# RF_AMP.net
KiCad netlist of a schematic drawn in Altium Designer
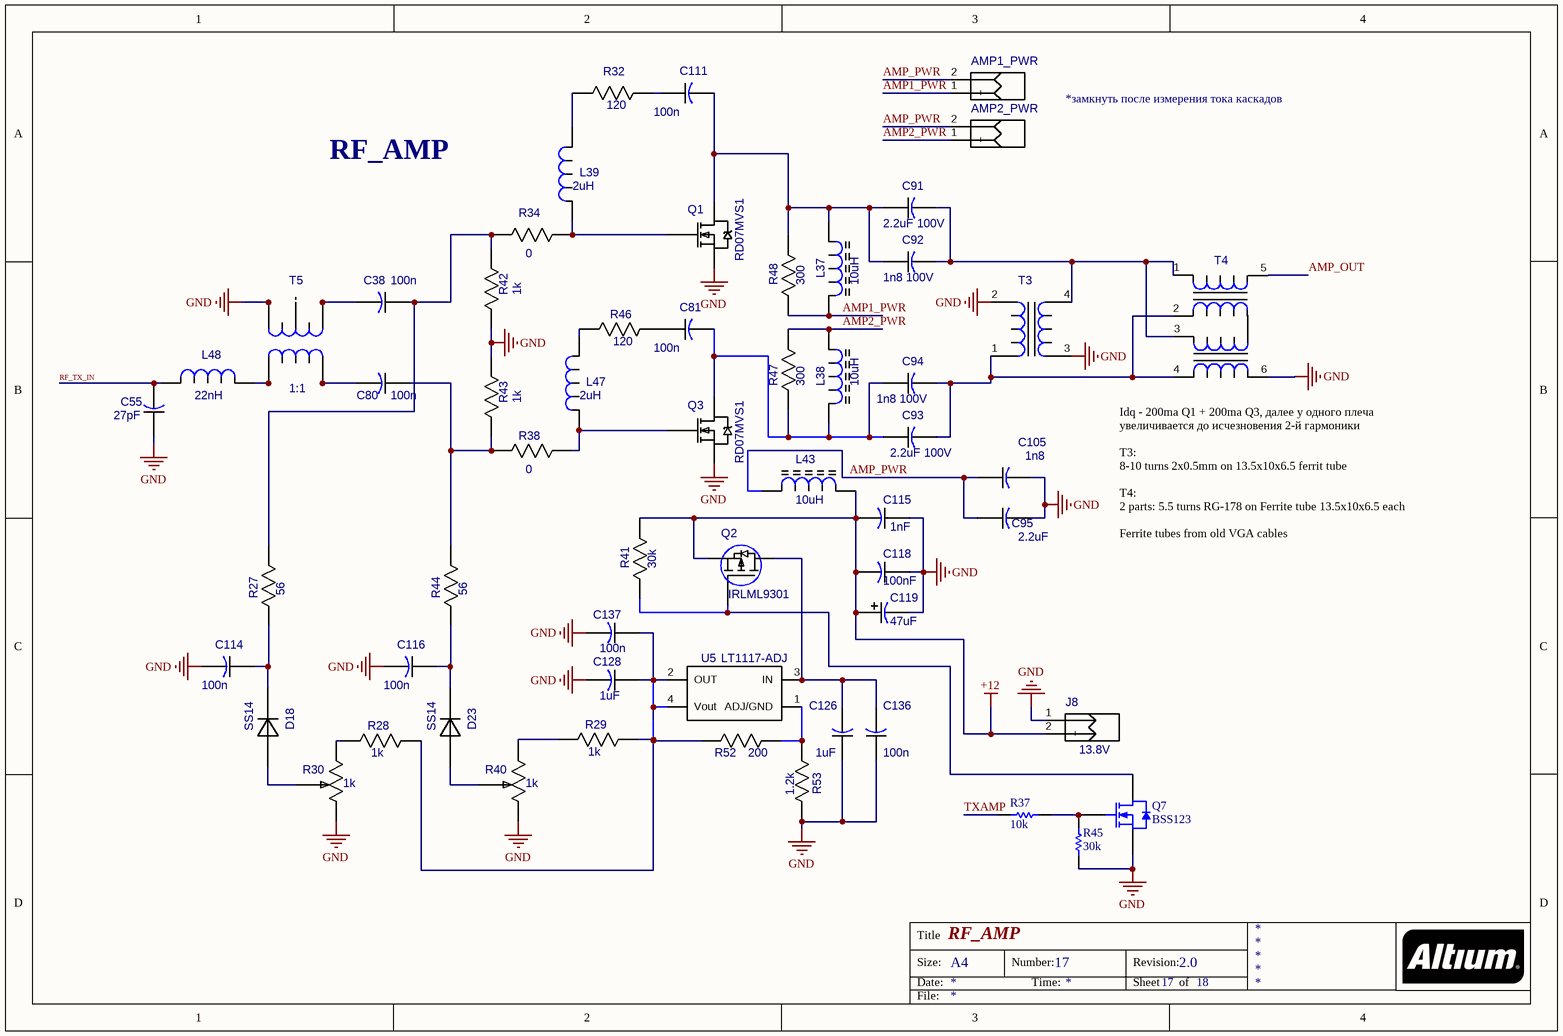
[diagram p0: RF_AMP.SchDoc]

(export (version "E")
  (design (tool "Eeschema 10.0.6"))
  (components
    (comp (ref "AMP1_PWR")
      (value "51022-0200")
      (footprint "51022-0200")
      (libsource (lib "*") (part "51022-0200"))
    )
    (comp (ref "AMP2_PWR")
      (value "51022-0200")
      (footprint "51022-0200")
      (libsource (lib "*") (part "51022-0200"))
    )
    (comp (ref "C38")
      (value "100n")
      (footprint "CAP_0805")
      (description "CAP_0805")
      (libsource (lib "*") (part "CAP_0805"))
    )
    (comp (ref "C55")
      (value "27pF")
      (footprint "CAP_0805")
      (description "CAP_0805")
      (libsource (lib "*") (part "CAP_0805"))
    )
    (comp (ref "C80")
      (value "100n")
      (footprint "CAP_0805")
      (description "CAP_0805")
      (libsource (lib "*") (part "CAP_0805"))
    )
    (comp (ref "C81")
      (value "100n")
      (footprint "CAP_1206")
      (description "CAP_1206")
      (libsource (lib "*") (part "CAP_1206"))
    )
    (comp (ref "C91")
      (value "2.2uF 100V")
      (footprint "CAP_1206")
      (description "CAP_1206")
      (libsource (lib "*") (part "CAP_1206"))
    )
    (comp (ref "C92")
      (value "1n8 100V")
      (footprint "CAP_1206")
      (description "CAP_1206")
      (libsource (lib "*") (part "CAP_1206"))
    )
    (comp (ref "C93")
      (value "2.2uF 100V")
      (footprint "CAP_1206")
      (description "CAP_1206")
      (libsource (lib "*") (part "CAP_1206"))
    )
    (comp (ref "C94")
      (value "1n8 100V")
      (footprint "CAP_1206")
      (description "CAP_1206")
      (libsource (lib "*") (part "CAP_1206"))
    )
    (comp (ref "C95")
      (value "2.2uF")
      (footprint "CAP_1206")
      (description "CAP_1206")
      (libsource (lib "*") (part "CAP_1206"))
    )
    (comp (ref "C105")
      (value "1n8")
      (footprint "CAP_1206")
      (description "CAP_1206")
      (libsource (lib "*") (part "CAP_1206"))
    )
    (comp (ref "C111")
      (value "100n")
      (footprint "CAP_1206")
      (description "CAP_1206")
      (libsource (lib "*") (part "CAP_1206"))
    )
    (comp (ref "C114")
      (value "100n")
      (footprint "CAP_0805")
      (description "CAP_0805")
      (libsource (lib "*") (part "CAP_0805"))
    )
    (comp (ref "C115")
      (value "1nF")
      (footprint "CAP_0805")
      (description "CAP_0805")
      (libsource (lib "*") (part "CAP_0805"))
    )
    (comp (ref "C116")
      (value "100n")
      (footprint "CAP_0805")
      (description "CAP_0805")
      (libsource (lib "*") (part "CAP_0805"))
    )
    (comp (ref "C118")
      (value "100nF")
      (footprint "CAP_0805")
      (description "CAP_0805")
      (libsource (lib "*") (part "CAP_0805"))
    )
    (comp (ref "C119")
      (value "47uF")
      (footprint "CAPAE_6.6x6.6h5.4")
      (description "CAPAE_6.6x6.6h5.4")
      (libsource (lib "*") (part "CAPAE_6.6x6.6h5.4"))
    )
    (comp (ref "C126")
      (value "1uF")
      (footprint "CAP_0805")
      (description "CAP_0805")
      (libsource (lib "*") (part "CAP_0805"))
    )
    (comp (ref "C128")
      (value "1uF")
      (footprint "CAP_0805")
      (description "CAP_0805")
      (libsource (lib "*") (part "CAP_0805"))
    )
    (comp (ref "C136")
      (value "100n")
      (footprint "CAP_0805")
      (description "CAP_0805")
      (libsource (lib "*") (part "CAP_0805"))
    )
    (comp (ref "C137")
      (value "100n")
      (footprint "CAP_0805")
      (description "CAP_0805")
      (libsource (lib "*") (part "CAP_0805"))
    )
    (comp (ref "D18") (value "SS14") (footprint "SS14") (libsource (lib "*") (part "SS14")))
    (comp (ref "D23") (value "SS14") (footprint "SS14") (libsource (lib "*") (part "SS14")))
    (comp (ref "J8")
      (value "13.8V")
      (footprint "1986717-2")
      (description "JX2")
      (libsource (lib "*") (part "1986717-2"))
    )
    (comp (ref "L37")
      (value "10uH")
      (footprint "IND_FERRITE_CORE")
      (description "Inductor")
      (libsource (lib "*") (part "IND_FERRITE_CORE"))
    )
    (comp (ref "L38")
      (value "10uH")
      (footprint "IND_FERRITE_CORE")
      (description "Inductor")
      (libsource (lib "*") (part "IND_FERRITE_CORE"))
    )
    (comp (ref "L39")
      (value "2uH")
      (footprint "IND_0805")
      (description "IND_0805")
      (libsource (lib "*") (part "IND_0805"))
    )
    (comp (ref "L43")
      (value "10uH")
      (footprint "IND_FERRITE_CORE")
      (description "Inductor")
      (libsource (lib "*") (part "IND_FERRITE_CORE"))
    )
    (comp (ref "L47")
      (value "2uH")
      (footprint "IND_0805")
      (description "IND_0805")
      (libsource (lib "*") (part "IND_0805"))
    )
    (comp (ref "L48")
      (value "22nH")
      (footprint "IND_0805")
      (description "IND_0805")
      (libsource (lib "*") (part "IND_0805"))
    )
    (comp (ref "Q1") (value "RD07MVS1") (footprint "RD07MVS1") (libsource (lib "*") (part "RD07MVS1")))
    (comp (ref "Q2")
      (value "IRLML9301")
      (footprint "SOT23")
      (description "MOSFET")
      (libsource (lib "*") (part "MOSFET_ENH_PD"))
    )
    (comp (ref "Q3") (value "RD07MVS1") (footprint "RD07MVS1") (libsource (lib "*") (part "RD07MVS1")))
    (comp (ref "Q7")
      (value "BSS123")
      (footprint "FAIR-SOT23-3_V")
      (fields (field (name "MANUFACTURER") "Fairchild"))
      (libsource (lib "Altium Content Vault") (part "NEMOS-GSD-3"))
    )
    (comp (ref "R27")
      (value "56")
      (footprint "RES_0805")
      (description "RES_0805")
      (libsource (lib "*") (part "RES_0805"))
    )
    (comp (ref "R28")
      (value "1k")
      (footprint "RES_0805")
      (description "RES_0805")
      (libsource (lib "*") (part "RES_0805"))
    )
    (comp (ref "R29")
      (value "1k")
      (footprint "RES_0805")
      (description "RES_0805")
      (libsource (lib "*") (part "RES_0805"))
    )
    (comp (ref "R30")
      (value "1k")
      (footprint "306J")
      (description "306J")
      (fields (field (name "Comment") "ADJ-1k"))
      (libsource (lib "*") (part "306J"))
    )
    (comp (ref "R32")
      (value "120")
      (footprint "RES_0805")
      (description "RES_0805")
      (libsource (lib "*") (part "RES_0805"))
    )
    (comp (ref "R34")
      (value "0")
      (footprint "RES_1206")
      (description "RES_1206")
      (libsource (lib "*") (part "RES_1206"))
    )
    (comp (ref "R37")
      (value "10k")
      (footprint "RESC2013X60X40NL20T25")
      (description "RES_0805")
      (fields (field (name "MANUFACTURER") "Panasonic") (field (name "PART NUMBER") "ERA-6AEB303V"))
      (libsource (lib "Altium Content Vault") (part "RES"))
    )
    (comp (ref "R38")
      (value "0")
      (footprint "RES_1206")
      (description "RES_1206")
      (libsource (lib "*") (part "RES_1206"))
    )
    (comp (ref "R40")
      (value "1k")
      (footprint "306J")
      (description "306J")
      (fields (field (name "Comment") "ADJ-1k"))
      (libsource (lib "*") (part "306J"))
    )
    (comp (ref "R41")
      (value "30k")
      (footprint "RES_0805")
      (description "RES_0805")
      (libsource (lib "*") (part "RES_0805"))
    )
    (comp (ref "R42")
      (value "1k")
      (footprint "RES_0805")
      (description "RES_0805")
      (libsource (lib "*") (part "RES_0805"))
    )
    (comp (ref "R43")
      (value "1k")
      (footprint "RES_0805")
      (description "RES_0805")
      (libsource (lib "*") (part "RES_0805"))
    )
    (comp (ref "R44")
      (value "56")
      (footprint "RES_0805")
      (description "RES_0805")
      (libsource (lib "*") (part "RES_0805"))
    )
    (comp (ref "R45")
      (value "30k")
      (footprint "RESC2013X60X40NL20T25")
      (description "RES_0805")
      (fields (field (name "MANUFACTURER") "Panasonic") (field (name "PART NUMBER") "ERA-6AEB303V"))
      (libsource (lib "Altium Content Vault") (part "RES"))
    )
    (comp (ref "R46")
      (value "120")
      (footprint "RES_0805")
      (description "RES_0805")
      (libsource (lib "*") (part "RES_0805"))
    )
    (comp (ref "R47")
      (value "300")
      (footprint "RES_1206")
      (description "RES_1206")
      (libsource (lib "*") (part "RES_1206"))
    )
    (comp (ref "R48")
      (value "300")
      (footprint "RES_1206")
      (description "RES_1206")
      (libsource (lib "*") (part "RES_1206"))
    )
    (comp (ref "R52")
      (value "200")
      (footprint "RES_0805")
      (description "RES_0805")
      (libsource (lib "*") (part "RES_0805"))
    )
    (comp (ref "R53")
      (value "1.2k")
      (footprint "RES_0805")
      (description "RES_0805")
      (libsource (lib "*") (part "RES_0805"))
    )
    (comp (ref "T3")
      (value "8T M2000HM 10*6*5")
      (footprint "Rutrof")
      (description "Transformer")
      (libsource (lib "*") (part "TRANSF_ICORE"))
    )
    (comp (ref "T4")
      (value "TRANSF_OUT")
      (footprint "TRANSF_OUT")
      (libsource (lib "RF-UNIT") (part "TRANSF_OUT_2"))
    )
    (comp (ref "T5")
      (value "1:1")
      (footprint "TRANSF_ACORE2")
      (libsource (lib "RF-UNIT_1") (part "TRANSF_ACORE2"))
    )
    (comp (ref "U5")
      (value "LT1117-ADJ")
      (footprint "LT1117IST-ADJ")
      (description "LT1117IST-ADJ")
      (libsource (lib "*") (part "LT1117IST-ADJ"))
    )
  )
  (nets
    (net (code "1") (name "+12") (class "Default")
      (node (ref "C115") (pin "2") (pinfunction "2_2") (pintype "passive"))
      (node (ref "C118") (pin "2") (pinfunction "2_2") (pintype "passive"))
      (node (ref "C119") (pin "1") (pinfunction "PLUS_1") (pintype "passive"))
      (node (ref "J8") (pin "2") (pinfunction "+_2") (pintype "passive"))
      (node (ref "L43") (pin "2") (pinfunction "B_2") (pintype "passive"))
      (node (ref "Q2") (pin "2") (pinfunction "S_2") (pintype "passive"))
      (node (ref "R41") (pin "2") (pinfunction "2_2") (pintype "passive"))
    )
    (net (code "2") (name "/AMP1_PWR") (class "Default")
      (node (ref "AMP1_PWR") (pin "1") (pinfunction "+_1") (pintype "passive"))
      (node (ref "L37") (pin "2") (pinfunction "B_2") (pintype "passive"))
      (node (ref "R48") (pin "1") (pinfunction "1_1") (pintype "passive"))
    )
    (net (code "3") (name "/AMP2_PWR") (class "Default")
      (node (ref "AMP2_PWR") (pin "1") (pinfunction "+_1") (pintype "passive"))
      (node (ref "L38") (pin "1") (pinfunction "A_1") (pintype "passive"))
      (node (ref "R47") (pin "2") (pinfunction "2_2") (pintype "passive"))
    )
    (net (code "4") (name "/AMP_OUT") (class "Default")
      (node (ref "T4") (pin "5") (pinfunction "OUT1_5") (pintype "passive"))
    )
    (net (code "5") (name "/AMP_PWR") (class "Default")
      (node (ref "AMP1_PWR") (pin "2") (pinfunction "-_2") (pintype "passive"))
      (node (ref "AMP2_PWR") (pin "2") (pinfunction "-_2") (pintype "passive"))
      (node (ref "C105") (pin "1") (pinfunction "1_1") (pintype "passive"))
      (node (ref "C95") (pin "1") (pinfunction "1_1") (pintype "passive"))
      (node (ref "L43") (pin "1") (pinfunction "A_1") (pintype "passive"))
    )
    (net (code "6") (name "/RF_TX_IN") (class "Default")
      (node (ref "C55") (pin "2") (pinfunction "2_2") (pintype "passive"))
      (node (ref "L48") (pin "1") (pinfunction "1_1") (pintype "passive"))
    )
    (net (code "7") (name "/TXAMP") (class "Default")
      (node (ref "R37") (pin "2") (pinfunction "2_2") (pintype "passive"))
    )
    (net (code "8") (name "GND") (class "Default")
      (node (ref "C105") (pin "2") (pinfunction "2_2") (pintype "passive"))
      (node (ref "C114") (pin "2") (pinfunction "2_2") (pintype "passive"))
      (node (ref "C115") (pin "1") (pinfunction "1_1") (pintype "passive"))
      (node (ref "C116") (pin "2") (pinfunction "2_2") (pintype "passive"))
      (node (ref "C118") (pin "1") (pinfunction "1_1") (pintype "passive"))
      (node (ref "C119") (pin "2") (pinfunction "MINUS_2") (pintype "passive"))
      (node (ref "C126") (pin "1") (pinfunction "1_1") (pintype "passive"))
      (node (ref "C128") (pin "2") (pinfunction "2_2") (pintype "passive"))
      (node (ref "C136") (pin "1") (pinfunction "1_1") (pintype "passive"))
      (node (ref "C137") (pin "2") (pinfunction "2_2") (pintype "passive"))
      (node (ref "C55") (pin "1") (pinfunction "1_1") (pintype "passive"))
      (node (ref "C95") (pin "2") (pinfunction "2_2") (pintype "passive"))
      (node (ref "J8") (pin "1") (pinfunction "-_1") (pintype "passive"))
      (node (ref "Q1") (pin "2") (pinfunction "S_2") (pintype "passive"))
      (node (ref "Q3") (pin "2") (pinfunction "S_2") (pintype "passive"))
      (node (ref "Q7") (pin "2") (pinfunction "S_2") (pintype "passive"))
      (node (ref "R30") (pin "1") (pinfunction "CCW_1") (pintype "passive"))
      (node (ref "R40") (pin "1") (pinfunction "CCW_1") (pintype "passive"))
      (node (ref "R42") (pin "1") (pinfunction "1_1") (pintype "passive"))
      (node (ref "R43") (pin "2") (pinfunction "2_2") (pintype "passive"))
      (node (ref "R45") (pin "1") (pinfunction "1_1") (pintype "passive"))
      (node (ref "R53") (pin "2") (pinfunction "2_2") (pintype "passive"))
      (node (ref "T3") (pin "2") (pinfunction "P2_2") (pintype "passive"))
      (node (ref "T3") (pin "3") (pinfunction "S1_3") (pintype "passive"))
      (node (ref "T4") (pin "6") (pinfunction "OUT2_6") (pintype "passive"))
      (node (ref "T5") (pin "3") (pinfunction "S3_3") (pintype "passive"))
      (node (ref "T5") (pin "9") (pinfunction "0_9") (pintype "passive"))
    )
    (net (code "9") (name "Net-(C38-Pad1)") (class "Default")
      (node (ref "C38") (pin "1") (pinfunction "1_1") (pintype "passive"))
      (node (ref "R27") (pin "2") (pinfunction "2_2") (pintype "passive"))
      (node (ref "R34") (pin "1") (pinfunction "1_1") (pintype "passive"))
      (node (ref "R42") (pin "2") (pinfunction "2_2") (pintype "passive"))
    )
    (net (code "10") (name "Net-(C80-Pad1)") (class "Default")
      (node (ref "C80") (pin "1") (pinfunction "1_1") (pintype "passive"))
      (node (ref "R38") (pin "1") (pinfunction "1_1") (pintype "passive"))
      (node (ref "R43") (pin "1") (pinfunction "1_1") (pintype "passive"))
      (node (ref "R44") (pin "2") (pinfunction "2_2") (pintype "passive"))
    )
    (net (code "11") (name "Net-(C81-Pad1)") (class "Default")
      (node (ref "C81") (pin "1") (pinfunction "1_1") (pintype "passive"))
      (node (ref "R46") (pin "2") (pinfunction "2_2") (pintype "passive"))
    )
    (net (code "12") (name "Net-(C111-Pad1)") (class "Default")
      (node (ref "C111") (pin "1") (pinfunction "1_1") (pintype "passive"))
      (node (ref "R32") (pin "2") (pinfunction "2_2") (pintype "passive"))
    )
    (net (code "13") (name "Net-(D18-A)") (class "Default")
      (node (ref "D18") (pin "2") (pinfunction "A_2") (pintype "passive"))
      (node (ref "R30") (pin "2") (pinfunction "W_2") (pintype "passive"))
    )
    (net (code "14") (name "Net-(D18-K)") (class "Default")
      (node (ref "C114") (pin "1") (pinfunction "1_1") (pintype "passive"))
      (node (ref "D18") (pin "1") (pinfunction "K_1") (pintype "passive"))
      (node (ref "R27") (pin "1") (pinfunction "1_1") (pintype "passive"))
    )
    (net (code "15") (name "Net-(D23-A)") (class "Default")
      (node (ref "D23") (pin "2") (pinfunction "A_2") (pintype "passive"))
      (node (ref "R40") (pin "2") (pinfunction "W_2") (pintype "passive"))
    )
    (net (code "16") (name "Net-(D23-K)") (class "Default")
      (node (ref "C116") (pin "1") (pinfunction "1_1") (pintype "passive"))
      (node (ref "D23") (pin "1") (pinfunction "K_1") (pintype "passive"))
      (node (ref "R44") (pin "1") (pinfunction "1_1") (pintype "passive"))
    )
    (net (code "17") (name "Net-(L37-A)") (class "Default")
      (node (ref "C111") (pin "2") (pinfunction "2_2") (pintype "passive"))
      (node (ref "C91") (pin "1") (pinfunction "1_1") (pintype "passive"))
      (node (ref "C92") (pin "1") (pinfunction "1_1") (pintype "passive"))
      (node (ref "L37") (pin "1") (pinfunction "A_1") (pintype "passive"))
      (node (ref "Q1") (pin "1") (pinfunction "D_1") (pintype "passive"))
      (node (ref "R48") (pin "2") (pinfunction "2_2") (pintype "passive"))
    )
    (net (code "18") (name "Net-(L38-B)") (class "Default")
      (node (ref "C81") (pin "2") (pinfunction "2_2") (pintype "passive"))
      (node (ref "C93") (pin "1") (pinfunction "1_1") (pintype "passive"))
      (node (ref "C94") (pin "1") (pinfunction "1_1") (pintype "passive"))
      (node (ref "L38") (pin "2") (pinfunction "B_2") (pintype "passive"))
      (node (ref "Q3") (pin "1") (pinfunction "D_1") (pintype "passive"))
      (node (ref "R47") (pin "1") (pinfunction "1_1") (pintype "passive"))
    )
    (net (code "19") (name "Net-(L39-Pad2)") (class "Default")
      (node (ref "L39") (pin "2") (pinfunction "2_2") (pintype "passive"))
      (node (ref "R32") (pin "1") (pinfunction "1_1") (pintype "passive"))
    )
    (net (code "20") (name "Net-(L47-Pad2)") (class "Default")
      (node (ref "L47") (pin "2") (pinfunction "2_2") (pintype "passive"))
      (node (ref "R46") (pin "1") (pinfunction "1_1") (pintype "passive"))
    )
    (net (code "21") (name "Net-(Q1-G)") (class "Default")
      (node (ref "L39") (pin "1") (pinfunction "1_1") (pintype "passive"))
      (node (ref "Q1") (pin "3") (pinfunction "G_3") (pintype "passive"))
      (node (ref "R34") (pin "2") (pinfunction "2_2") (pintype "passive"))
    )
    (net (code "22") (name "Net-(Q2-D)") (class "Default")
      (node (ref "C126") (pin "2") (pinfunction "2_2") (pintype "passive"))
      (node (ref "C136") (pin "2") (pinfunction "2_2") (pintype "passive"))
      (node (ref "Q2") (pin "3") (pinfunction "D_3") (pintype "passive"))
      (node (ref "U5") (pin "3") (pinfunction "IN_3") (pintype "passive"))
    )
    (net (code "23") (name "Net-(Q2-G)") (class "Default")
      (node (ref "Q2") (pin "1") (pinfunction "G_1") (pintype "passive"))
      (node (ref "Q7") (pin "3") (pinfunction "D_3") (pintype "passive"))
      (node (ref "R41") (pin "1") (pinfunction "1_1") (pintype "passive"))
    )
    (net (code "24") (name "Net-(Q3-G)") (class "Default")
      (node (ref "L47") (pin "1") (pinfunction "1_1") (pintype "passive"))
      (node (ref "Q3") (pin "3") (pinfunction "G_3") (pintype "passive"))
      (node (ref "R38") (pin "2") (pinfunction "2_2") (pintype "passive"))
    )
    (net (code "25") (name "Net-(Q7-G)") (class "Default")
      (node (ref "Q7") (pin "1") (pinfunction "G_1") (pintype "passive"))
      (node (ref "R37") (pin "1") (pinfunction "1_1") (pintype "passive"))
      (node (ref "R45") (pin "2") (pinfunction "2_2") (pintype "passive"))
    )
    (net (code "26") (name "Net-(R30-CW)") (class "Default")
      (node (ref "R28") (pin "1") (pinfunction "1_1") (pintype "passive"))
      (node (ref "R30") (pin "3") (pinfunction "CW_3") (pintype "passive"))
    )
    (net (code "27") (name "Net-(R40-CW)") (class "Default")
      (node (ref "R29") (pin "1") (pinfunction "1_1") (pintype "passive"))
      (node (ref "R40") (pin "3") (pinfunction "CW_3") (pintype "passive"))
    )
    (net (code "28") (name "Net-(T3-P1)") (class "Default")
      (node (ref "C93") (pin "2") (pinfunction "2_2") (pintype "passive"))
      (node (ref "C94") (pin "2") (pinfunction "2_2") (pintype "passive"))
      (node (ref "T3") (pin "1") (pinfunction "P1_1") (pintype "passive"))
      (node (ref "T4") (pin "2") (pinfunction "T1N_2") (pintype "passive"))
      (node (ref "T4") (pin "4") (pinfunction "T2P_4") (pintype "passive"))
    )
    (net (code "29") (name "Net-(T3-S2)") (class "Default")
      (node (ref "C91") (pin "2") (pinfunction "2_2") (pintype "passive"))
      (node (ref "C92") (pin "2") (pinfunction "2_2") (pintype "passive"))
      (node (ref "T3") (pin "4") (pinfunction "S2_4") (pintype "passive"))
      (node (ref "T4") (pin "1") (pinfunction "T1P_1") (pintype "passive"))
      (node (ref "T4") (pin "3") (pinfunction "T2N_3") (pintype "passive"))
    )
    (net (code "30") (name "Net-(T5-P1)") (class "Default")
      (node (ref "C80") (pin "2") (pinfunction "2_2") (pintype "passive"))
      (node (ref "T5") (pin "10") (pinfunction "0_10") (pintype "passive"))
      (node (ref "T5") (pin "6") (pinfunction "P1_6") (pintype "passive"))
    )
    (net (code "31") (name "Net-(T5-P2)") (class "Default")
      (node (ref "L48") (pin "2") (pinfunction "2_2") (pintype "passive"))
      (node (ref "T5") (pin "11") (pinfunction "0_11") (pintype "passive"))
      (node (ref "T5") (pin "4") (pinfunction "P2_4") (pintype "passive"))
    )
    (net (code "32") (name "Net-(T5-S1)") (class "Default")
      (node (ref "C38") (pin "2") (pinfunction "2_2") (pintype "passive"))
      (node (ref "T5") (pin "1") (pinfunction "S1_1") (pintype "passive"))
      (node (ref "T5") (pin "7") (pinfunction "0_7") (pintype "passive"))
    )
    (net (code "33") (name "Net-(U5-ADJ{slash}GND)") (class "Default")
      (node (ref "R52") (pin "2") (pinfunction "2_2") (pintype "passive"))
      (node (ref "R53") (pin "1") (pinfunction "1_1") (pintype "passive"))
      (node (ref "U5") (pin "1") (pinfunction "ADJ/GND_1") (pintype "passive"))
    )
    (net (code "34") (name "Net-(U5-OUT)") (class "Default")
      (node (ref "C128") (pin "1") (pinfunction "1_1") (pintype "passive"))
      (node (ref "C137") (pin "1") (pinfunction "1_1") (pintype "passive"))
      (node (ref "R28") (pin "2") (pinfunction "2_2") (pintype "passive"))
      (node (ref "R29") (pin "2") (pinfunction "2_2") (pintype "passive"))
      (node (ref "R52") (pin "1") (pinfunction "1_1") (pintype "passive"))
      (node (ref "U5") (pin "2") (pinfunction "OUT_2") (pintype "passive"))
      (node (ref "U5") (pin "4") (pinfunction "Vout_4") (pintype "passive"))
    )
    (net (code "35") (name "unconnected-(T5-S2-Pad2)") (class "Default")
      (node (ref "T5") (pin "2") (pinfunction "S2_2") (pintype "passive"))
    )
    (net (code "36") (name "unconnected-(T5-S2-Pad8)") (class "Default")
      (node (ref "T5") (pin "8") (pinfunction "S2_8") (pintype "passive"))
    )
  )
)
